# Pool_Interface.net
KiCad netlist of a schematic drawn in EAGLE
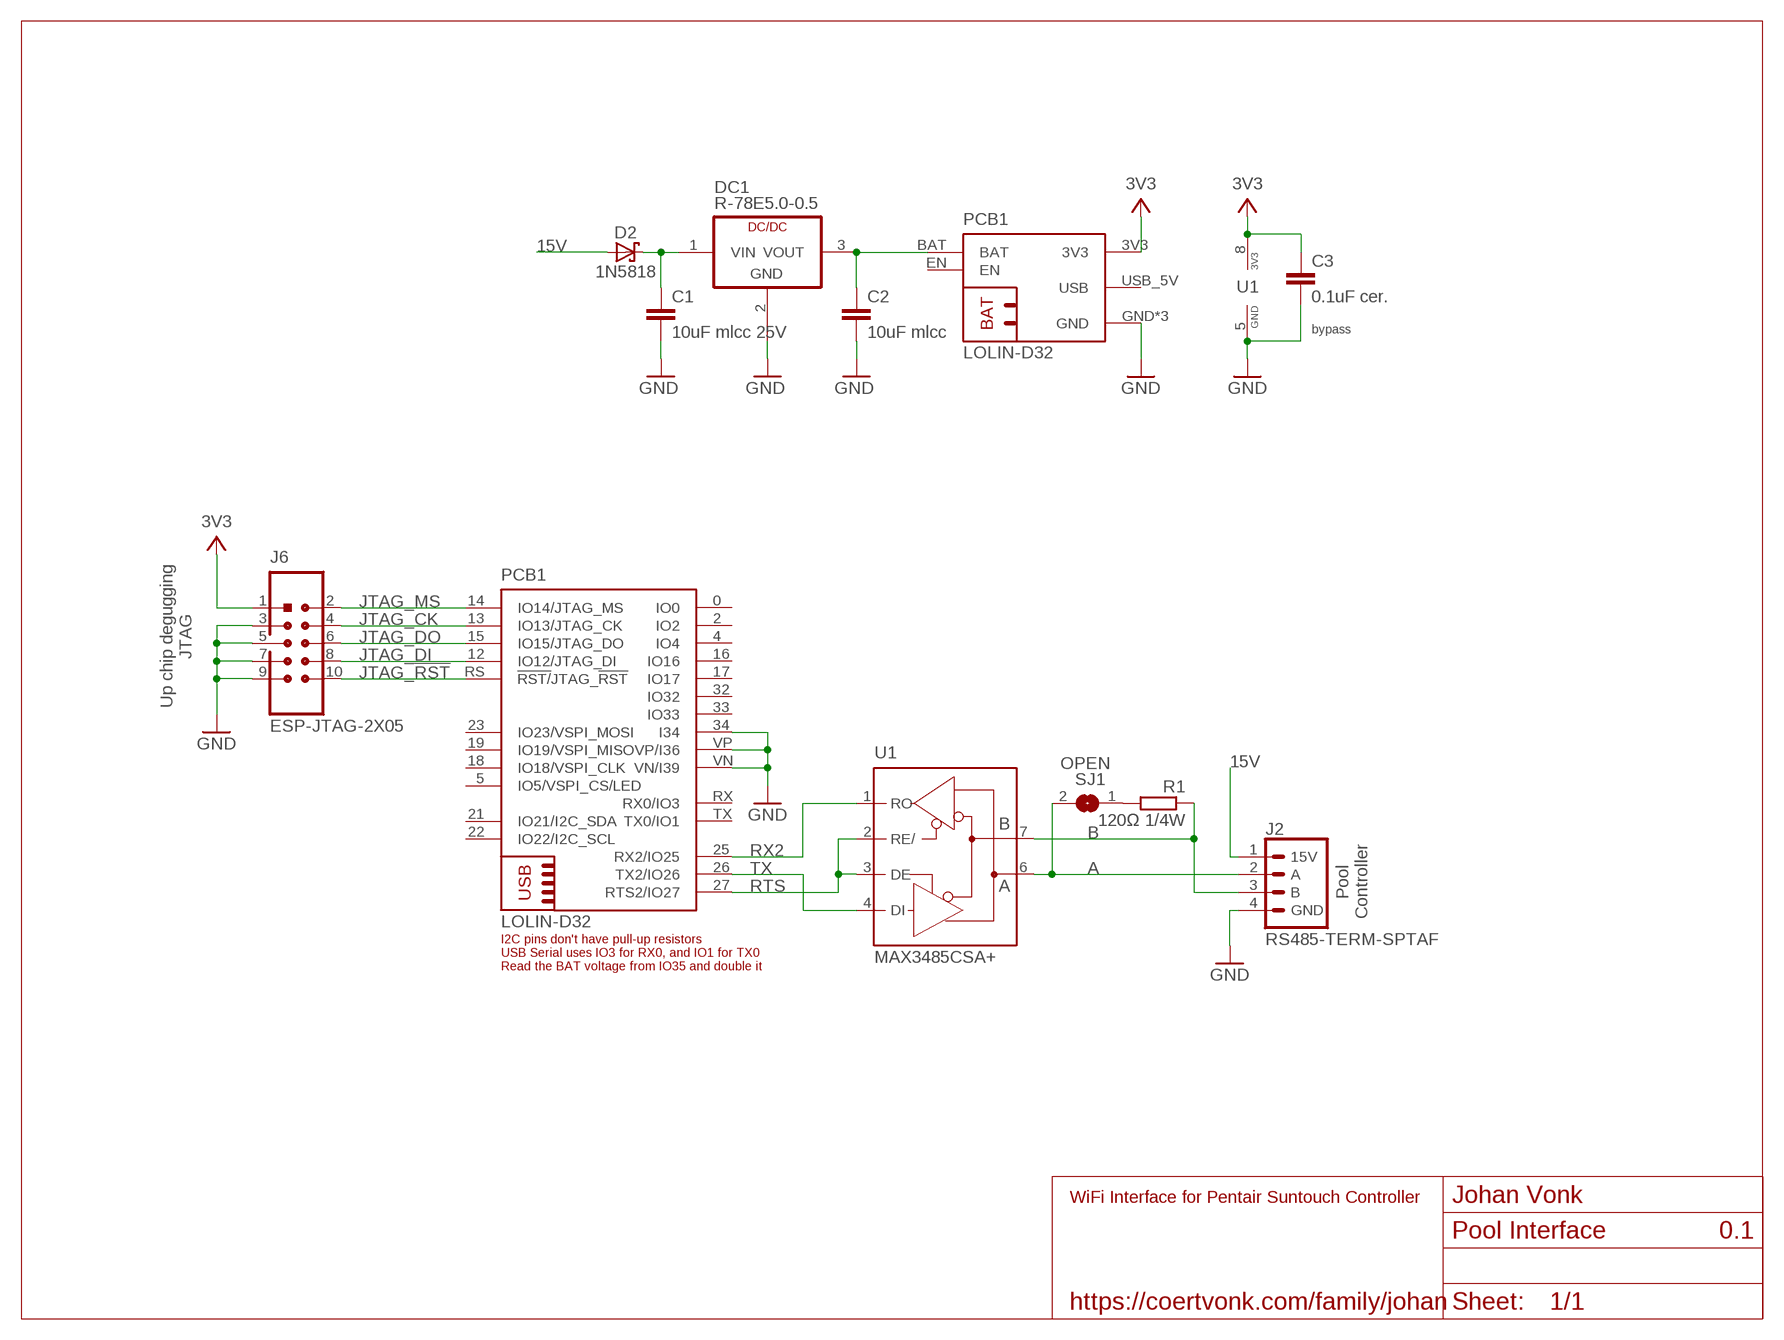
[diagram p0: schematic, sheet 1]

(export (version "E")
  (design (tool "Eeschema 10.0.6"))
  (components
    (comp (ref "C1")
      (value "10uF mlcc 25V")
      (footprint "eagle-import:C0805K")
      (fields (field (name "MANF") "Murata Electronics"))
      (libsource (lib "eagle-import") (part "C-EUC0805K"))
    )
    (comp (ref "C2")
      (value "10uF mlcc")
      (footprint "eagle-import:C0805K")
      (fields (field (name "MANF") "Murata Electronics"))
      (libsource (lib "eagle-import") (part "C-EUC0805K"))
    )
    (comp (ref "C3")
      (value "0.1uF cer.")
      (footprint "eagle-import:C0805K")
      (fields (field (name "MANF") "KEMET"))
      (libsource (lib "eagle-import") (part "C-EUC0805K"))
    )
    (comp (ref "D2")
      (value "1N5818")
      (footprint "eagle-import:DO41-7.6")
      (fields (field (name "MANF") "Rectron"))
      (libsource (lib "eagle-import") (part "1N5818"))
    )
    (comp (ref "DC1")
      (value "R-78E5.0-0.5")
      (footprint "eagle-import:SIP3")
      (fields (field (name "MANF") "RECOM Power"))
      (libsource (lib "eagle-import") (part "R-78E-0.55.0"))
    )
    (comp (ref "J2")
      (value "RS485-TERM-SPTAF")
      (footprint "eagle-import:SPTAF1_4-5,0-LL")
      (fields (field (name "MANF") "Phoenix Contact"))
      (libsource (lib "eagle-import") (part "RS485-TERM-SPTAF"))
    )
    (comp (ref "J6")
      (value "ESP-JTAG-2X05")
      (footprint "eagle-import:2X05_SHROUDED")
      (fields (field (name "MANF") "Molex"))
      (libsource (lib "eagle-import") (part "ESP-JTAG-2X05"))
    )
    (comp (ref "PCB1")
      (value "LOLIN-D32")
      (footprint "eagle-import:LOLIN-D32")
      (fields
        (field (name "MANF") "WEMOS Electronics")
        (field (name "ALIEXPRESS#") "32808551116")
        (field (name "MANF#") "D32")
      )
      (libsource (lib "eagle-import") (part "LOLIN-D32"))
    )
    (comp (ref "R1")
      (value "120Ω 1/4W")
      (footprint "eagle-import:R0805")
      (fields (field (name "MANF") "Bourns"))
      (libsource (lib "eagle-import") (part "R-EU_R0805"))
    )
    (comp (ref "SJ1")
      (value "OPEN")
      (footprint "eagle-import:SJ")
      (libsource (lib "eagle-import") (part "SJ"))
    )
    (comp (ref "U1")
      (value "MAX3485CSA+")
      (footprint "eagle-import:SO08")
      (fields
        (field (name "MF") "MAXIM")
        (field (name "MPN") "MAX481CSA")
        (field (name "MANF") "Maxim Integrated")
        (field (name "MANF#") "MAX3485CSA+")
        (field (name "MOUSER#") "700-MAX3485CSA")
      )
      (libsource (lib "eagle-import") (part "MAX3485CSA+"))
    )
  )
  (nets
    (net (code "1") (name "/15V") (class "Default")
      (node (ref "D2") (pin "A") (pinfunction "A_A") (pintype "passive"))
      (node (ref "J2") (pin "1") (pinfunction "15V_1") (pintype "power_in"))
    )
    (net (code "2") (name "/A") (class "Default")
      (node (ref "J2") (pin "2") (pinfunction "A_2") (pintype "passive"))
      (node (ref "SJ1") (pin "2") (pinfunction "2_2") (pintype "passive"))
      (node (ref "U1") (pin "6") (pinfunction "A_6") (pintype "passive"))
    )
    (net (code "3") (name "/B") (class "Default")
      (node (ref "J2") (pin "3") (pinfunction "B_3") (pintype "passive"))
      (node (ref "R1") (pin "1") (pinfunction "1_1") (pintype "passive"))
      (node (ref "U1") (pin "7") (pinfunction "B_7") (pintype "passive"))
    )
    (net (code "4") (name "/JTAG_CK") (class "Default")
      (node (ref "J6") (pin "4") (pinfunction "TCK_4") (pintype "passive"))
      (node (ref "PCB1") (pin "13") (pinfunction "IO13/JTAG_CK_13") (pintype "bidirectional"))
    )
    (net (code "5") (name "/JTAG_DI") (class "Default")
      (node (ref "J6") (pin "8") (pinfunction "TDI_8") (pintype "passive"))
      (node (ref "PCB1") (pin "12") (pinfunction "IO12/JTAG_DI_12") (pintype "bidirectional"))
    )
    (net (code "6") (name "/JTAG_DO") (class "Default")
      (node (ref "J6") (pin "6") (pinfunction "TDO_6") (pintype "passive"))
      (node (ref "PCB1") (pin "15") (pinfunction "IO15/JTAG_DO_15") (pintype "bidirectional"))
    )
    (net (code "7") (name "/JTAG_MS") (class "Default")
      (node (ref "J6") (pin "2") (pinfunction "TMS_2") (pintype "passive"))
      (node (ref "PCB1") (pin "14") (pinfunction "IO14/JTAG_MS_14") (pintype "bidirectional"))
    )
    (net (code "8") (name "/JTAG_~{RST}") (class "Default")
      (node (ref "J6") (pin "10") (pinfunction "NC_10") (pintype "passive"))
      (node (ref "PCB1") (pin "RS") (pinfunction "~{RST/}JTAG_~{RST}_RS") (pintype "input"))
    )
    (net (code "9") (name "/RTS") (class "Default")
      (node (ref "PCB1") (pin "27") (pinfunction "RTS2/IO27_27") (pintype "bidirectional"))
      (node (ref "U1") (pin "2") (pinfunction "RE/_2") (pintype "input"))
      (node (ref "U1") (pin "3") (pinfunction "DE_3") (pintype "input"))
    )
    (net (code "10") (name "/RX2") (class "Default")
      (node (ref "PCB1") (pin "25") (pinfunction "RX2/IO25_25") (pintype "bidirectional"))
      (node (ref "U1") (pin "1") (pinfunction "RO_1") (pintype "output"))
    )
    (net (code "11") (name "/TX") (class "Default")
      (node (ref "PCB1") (pin "26") (pinfunction "TX2/IO26_26") (pintype "bidirectional"))
      (node (ref "U1") (pin "4") (pinfunction "DI_4") (pintype "input"))
    )
    (net (code "12") (name "/USB") (class "Default")
      (node (ref "PCB1") (pin "USB_5V") (pinfunction "USB_USB_5V") (pintype "power_in"))
    )
    (net (code "13") (name "3V3") (class "Default")
      (node (ref "C3") (pin "1") (pinfunction "1_1") (pintype "passive"))
      (node (ref "J6") (pin "1") (pinfunction "3V3_1") (pintype "power_in"))
      (node (ref "PCB1") (pin "3V3") (pinfunction "3V3_3V3") (pintype "power_in"))
      (node (ref "U1") (pin "8") (pinfunction "VCC_8") (pintype "passive"))
    )
    (net (code "14") (name "GND") (class "Default")
      (node (ref "C1") (pin "2") (pinfunction "2_2") (pintype "passive"))
      (node (ref "C2") (pin "2") (pinfunction "2_2") (pintype "passive"))
      (node (ref "C3") (pin "2") (pinfunction "2_2") (pintype "passive"))
      (node (ref "DC1") (pin "2") (pinfunction "GND_2") (pintype "power_in"))
      (node (ref "J2") (pin "4") (pinfunction "GND_4") (pintype "power_in"))
      (node (ref "J6") (pin "3") (pinfunction "GND_3") (pintype "power_in"))
      (node (ref "J6") (pin "5") (pinfunction "GND_5") (pintype "power_in"))
      (node (ref "J6") (pin "7") (pinfunction "GND_7") (pintype "power_in"))
      (node (ref "J6") (pin "9") (pinfunction "GND_9") (pintype "power_in"))
      (node (ref "PCB1") (pin "34") (pinfunction "I34_34") (pintype "input"))
      (node (ref "PCB1") (pin "GND") (pinfunction "GND_GND") (pintype "power_in"))
      (node (ref "PCB1") (pin "GND@1") (pinfunction "GND_GND@1") (pintype "power_in"))
      (node (ref "PCB1") (pin "GND@2") (pinfunction "GND_GND@2") (pintype "power_in"))
      (node (ref "PCB1") (pin "VN") (pinfunction "VN/I39_VN") (pintype "input"))
      (node (ref "PCB1") (pin "VP") (pinfunction "VP/I36_VP") (pintype "input"))
      (node (ref "U1") (pin "5") (pinfunction "GND_5") (pintype "power_in"))
    )
    (net (code "15") (name "Net-(DC1-VIN)") (class "Default")
      (node (ref "C1") (pin "1") (pinfunction "1_1") (pintype "passive"))
      (node (ref "D2") (pin "C") (pinfunction "C_C") (pintype "passive"))
      (node (ref "DC1") (pin "1") (pinfunction "VIN_1") (pintype "power_in"))
    )
    (net (code "16") (name "Net-(DC1-VOUT)") (class "Default")
      (node (ref "C2") (pin "1") (pinfunction "1_1") (pintype "passive"))
      (node (ref "DC1") (pin "3") (pinfunction "VOUT_3") (pintype "power_in"))
      (node (ref "PCB1") (pin "BAT") (pinfunction "BAT_BAT") (pintype "power_in"))
    )
    (net (code "17") (name "Net-(R1-Pad2)") (class "Default")
      (node (ref "R1") (pin "2") (pinfunction "2_2") (pintype "passive"))
      (node (ref "SJ1") (pin "1") (pinfunction "1_1") (pintype "passive"))
    )
    (net (code "18") (name "unconnected-(PCB1-PadEN)") (class "Default")
      (node (ref "PCB1") (pin "EN") (pinfunction "EN_EN") (pintype "passive"))
    )
    (net (code "19") (name "unconnected-(PCB1A-IO0-Pad0)") (class "Default")
      (node (ref "PCB1") (pin "0") (pinfunction "IO0_0") (pintype "bidirectional"))
    )
    (net (code "20") (name "unconnected-(PCB1A-IO2-Pad2)") (class "Default")
      (node (ref "PCB1") (pin "2") (pinfunction "IO2_2") (pintype "bidirectional"))
    )
    (net (code "21") (name "unconnected-(PCB1A-IO4-Pad4)") (class "Default")
      (node (ref "PCB1") (pin "4") (pinfunction "IO4_4") (pintype "bidirectional"))
    )
    (net (code "22") (name "unconnected-(PCB1A-IO5{slash}VSPI_CS{slash}LED-Pad5)") (class "Default")
      (node (ref "PCB1") (pin "5") (pinfunction "IO5/VSPI_CS/LED_5") (pintype "bidirectional"))
    )
    (net (code "23") (name "unconnected-(PCB1A-IO16-Pad16)") (class "Default")
      (node (ref "PCB1") (pin "16") (pinfunction "IO16_16") (pintype "bidirectional"))
    )
    (net (code "24") (name "unconnected-(PCB1A-IO17-Pad17)") (class "Default")
      (node (ref "PCB1") (pin "17") (pinfunction "IO17_17") (pintype "bidirectional"))
    )
    (net (code "25") (name "unconnected-(PCB1A-IO18{slash}VSPI_CLK-Pad18)") (class "Default")
      (node (ref "PCB1") (pin "18") (pinfunction "IO18/VSPI_CLK_18") (pintype "bidirectional"))
    )
    (net (code "26") (name "unconnected-(PCB1A-IO19{slash}VSPI_MISO-Pad19)") (class "Default")
      (node (ref "PCB1") (pin "19") (pinfunction "IO19/VSPI_MISO_19") (pintype "bidirectional"))
    )
    (net (code "27") (name "unconnected-(PCB1A-IO21{slash}I2C_SDA-Pad21)") (class "Default")
      (node (ref "PCB1") (pin "21") (pinfunction "IO21/I2C_SDA_21") (pintype "bidirectional"))
    )
    (net (code "28") (name "unconnected-(PCB1A-IO22{slash}I2C_SCL-Pad22)") (class "Default")
      (node (ref "PCB1") (pin "22") (pinfunction "IO22/I2C_SCL_22") (pintype "bidirectional"))
    )
    (net (code "29") (name "unconnected-(PCB1A-IO23{slash}VSPI_MOSI-Pad23)") (class "Default")
      (node (ref "PCB1") (pin "23") (pinfunction "IO23/VSPI_MOSI_23") (pintype "bidirectional"))
    )
    (net (code "30") (name "unconnected-(PCB1A-IO32-Pad32)") (class "Default")
      (node (ref "PCB1") (pin "32") (pinfunction "IO32_32") (pintype "bidirectional"))
    )
    (net (code "31") (name "unconnected-(PCB1A-IO33-Pad33)") (class "Default")
      (node (ref "PCB1") (pin "33") (pinfunction "IO33_33") (pintype "bidirectional"))
    )
    (net (code "32") (name "unconnected-(PCB1A-RX0{slash}IO3-PadRX)") (class "Default")
      (node (ref "PCB1") (pin "RX") (pinfunction "RX0/IO3_RX") (pintype "bidirectional"))
    )
    (net (code "33") (name "unconnected-(PCB1A-TX0{slash}IO1-PadTX)") (class "Default")
      (node (ref "PCB1") (pin "TX") (pinfunction "TX0/IO1_TX") (pintype "bidirectional"))
    )
  )
)
